# Camera.net
KiCad netlist of a schematic drawn in Altium Designer
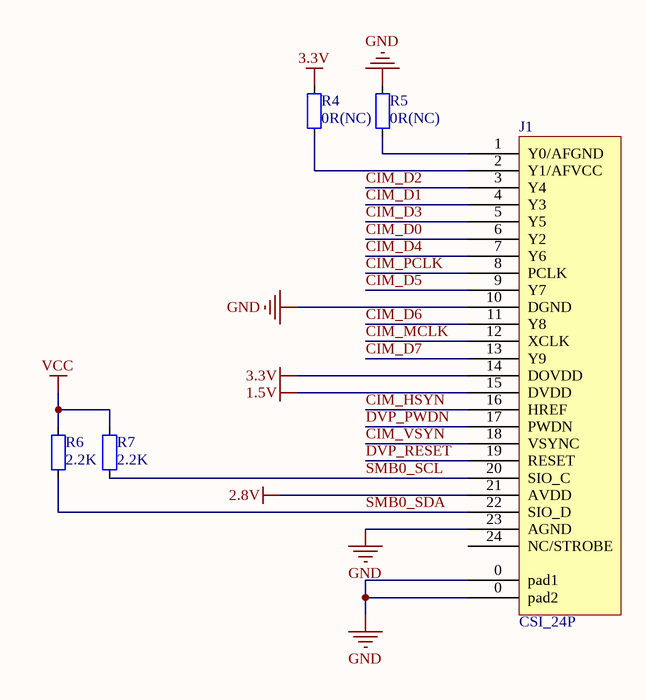
[diagram p0: Camera.SchDoc]

(export (version "E")
  (design (tool "Eeschema 10.0.6"))
  (components
    (comp (ref "J1")
      (value "CSI_24P")
      (footprint "FFC_0.5_24")
      (libsource (lib "LicheeDan") (part "CSI_24P"))
    )
    (comp (ref "R4")
      (value "0R(NC)")
      (footprint "PCB_PassiveRes:RES_0402")
      (description "Resistor")
      (fields (field (name "Comment") "Res_0402"))
      (libsource (lib "SCH_Passive") (part "Res_0402"))
    )
    (comp (ref "R5")
      (value "0R(NC)")
      (footprint "PCB_PassiveRes:RES_0402")
      (description "Resistor")
      (fields (field (name "Comment") "Res_0402"))
      (libsource (lib "SCH_Passive") (part "Res_0402"))
    )
    (comp (ref "R6")
      (value "2.2K")
      (footprint "PCB_PassiveRes:RES_0402")
      (description "Resistor")
      (fields (field (name "Comment") "Res_0402"))
      (libsource (lib "SCH_Passive") (part "Res_0402"))
    )
    (comp (ref "R7")
      (value "2.2K")
      (footprint "PCB_PassiveRes:RES_0402")
      (description "Resistor")
      (fields (field (name "Comment") "Res_0402"))
      (libsource (lib "SCH_Passive") (part "Res_0402"))
    )
  )
  (nets
    (net (code "1") (name "/CIM_D0") (class "Default")
      (node (ref "J1") (pin "6") (pinfunction "Y2_6") (pintype "passive"))
    )
    (net (code "2") (name "/CIM_D1") (class "Default")
      (node (ref "J1") (pin "4") (pinfunction "Y3_4") (pintype "passive"))
    )
    (net (code "3") (name "/CIM_D2") (class "Default")
      (node (ref "J1") (pin "3") (pinfunction "Y4_3") (pintype "passive"))
    )
    (net (code "4") (name "/CIM_D3") (class "Default")
      (node (ref "J1") (pin "5") (pinfunction "Y5_5") (pintype "passive"))
    )
    (net (code "5") (name "/CIM_D4") (class "Default")
      (node (ref "J1") (pin "7") (pinfunction "Y6_7") (pintype "passive"))
    )
    (net (code "6") (name "/CIM_D5") (class "Default")
      (node (ref "J1") (pin "9") (pinfunction "Y7_9") (pintype "passive"))
    )
    (net (code "7") (name "/CIM_D6") (class "Default")
      (node (ref "J1") (pin "11") (pinfunction "Y8_11") (pintype "passive"))
    )
    (net (code "8") (name "/CIM_D7") (class "Default")
      (node (ref "J1") (pin "13") (pinfunction "Y9_13") (pintype "passive"))
    )
    (net (code "9") (name "/CIM_HSYN") (class "Default")
      (node (ref "J1") (pin "16") (pinfunction "HREF_16") (pintype "passive"))
    )
    (net (code "10") (name "/CIM_MCLK") (class "Default")
      (node (ref "J1") (pin "12") (pinfunction "XCLK_12") (pintype "passive"))
    )
    (net (code "11") (name "/CIM_PCLK") (class "Default")
      (node (ref "J1") (pin "8") (pinfunction "PCLK_8") (pintype "passive"))
    )
    (net (code "12") (name "/CIM_VSYN") (class "Default")
      (node (ref "J1") (pin "18") (pinfunction "VSYNC_18") (pintype "passive"))
    )
    (net (code "13") (name "/DVP_PWDN") (class "Default")
      (node (ref "J1") (pin "17") (pinfunction "PWDN_17") (pintype "passive"))
    )
    (net (code "14") (name "/DVP_RESET") (class "Default")
      (node (ref "J1") (pin "19") (pinfunction "RESET_19") (pintype "passive"))
    )
    (net (code "15") (name "/SMB0_SCL") (class "Default")
      (node (ref "J1") (pin "20") (pinfunction "SIO_C_20") (pintype "passive"))
      (node (ref "R7") (pin "1") (pinfunction "1_1") (pintype "passive"))
    )
    (net (code "16") (name "/SMB0_SDA") (class "Default")
      (node (ref "J1") (pin "22") (pinfunction "SIO_D_22") (pintype "passive"))
      (node (ref "R6") (pin "1") (pinfunction "1_1") (pintype "passive"))
    )
    (net (code "17") (name "1.5V") (class "Default")
      (node (ref "J1") (pin "15") (pinfunction "DVDD_15") (pintype "passive"))
    )
    (net (code "18") (name "2.8V") (class "Default")
      (node (ref "J1") (pin "21") (pinfunction "AVDD_21") (pintype "passive"))
    )
    (net (code "19") (name "3.3V") (class "Default")
      (node (ref "J1") (pin "14") (pinfunction "DOVDD_14") (pintype "passive"))
      (node (ref "R4") (pin "2") (pinfunction "2_2") (pintype "passive"))
    )
    (net (code "20") (name "GND") (class "Default")
      (node (ref "J1") (pin "0") (pinfunction "pad1_0") (pintype "passive"))
      (node (ref "J1") (pin "10") (pinfunction "DGND_10") (pintype "passive"))
      (node (ref "J1") (pin "23") (pinfunction "AGND_23") (pintype "passive"))
      (node (ref "R5") (pin "2") (pinfunction "2_2") (pintype "passive"))
    )
    (net (code "21") (name "Net-(J1-Y0{slash}AFGND)") (class "Default")
      (node (ref "J1") (pin "1") (pinfunction "Y0/AFGND_1") (pintype "passive"))
      (node (ref "R5") (pin "1") (pinfunction "1_1") (pintype "passive"))
    )
    (net (code "22") (name "Net-(J1-Y1{slash}AFVCC)") (class "Default")
      (node (ref "J1") (pin "2") (pinfunction "Y1/AFVCC_2") (pintype "passive"))
      (node (ref "R4") (pin "1") (pinfunction "1_1") (pintype "passive"))
    )
    (net (code "23") (name "VCC") (class "Default")
      (node (ref "R6") (pin "2") (pinfunction "2_2") (pintype "passive"))
      (node (ref "R7") (pin "2") (pinfunction "2_2") (pintype "passive"))
    )
    (net (code "24") (name "unconnected-(J1-NC{slash}STROBE-Pad24)") (class "Default")
      (node (ref "J1") (pin "24") (pinfunction "NC/STROBE_24") (pintype "passive"))
    )
  )
)
